# LTC3260.net
KiCad netlist of a schematic drawn in Altium Designer
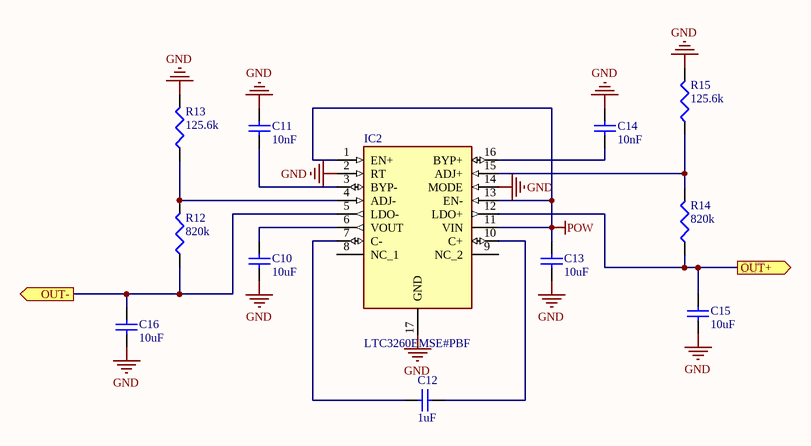
[diagram p0: LTC3260.SchDoc]

(export (version "E")
  (design (tool "Eeschema 10.0.6"))
  (components
    (comp (ref "C10")
      (value "10uF")
      (footprint "0805 CAP")
      (fields
        (field (name "MANUFACTURER") "Murata")
        (field (name "MANUFACTURER PART NUMBER") "GCM21BR7YA105KA55L")
      )
      (libsource (lib "charger_LT3652") (part "1uF/0805"))
    )
    (comp (ref "C11")
      (value "10nF")
      (footprint "0603 RES")
      (fields
        (field (name "MANUFACTURER") "Murata")
        (field (name "MANUFACTURER PART NUMBER") "GCM21BR7YA105KA55L")
      )
      (libsource (lib "charger_LT3652") (part "1uF/0805"))
    )
    (comp (ref "C12")
      (value "1uF")
      (footprint "0805 CAP")
      (fields
        (field (name "MANUFACTURER") "Murata")
        (field (name "MANUFACTURER PART NUMBER") "GCM21BR7YA105KA55L")
      )
      (libsource (lib "charger_LT3652") (part "1uF/0805"))
    )
    (comp (ref "C13")
      (value "10uF")
      (footprint "0805 CAP")
      (fields
        (field (name "MANUFACTURER") "Murata")
        (field (name "MANUFACTURER PART NUMBER") "GCM21BR7YA105KA55L")
      )
      (libsource (lib "charger_LT3652") (part "1uF/0805"))
    )
    (comp (ref "C14")
      (value "10nF")
      (footprint "0603 RES")
      (fields
        (field (name "MANUFACTURER") "Murata")
        (field (name "MANUFACTURER PART NUMBER") "GCM21BR7YA105KA55L")
      )
      (libsource (lib "charger_LT3652") (part "1uF/0805"))
    )
    (comp (ref "C15")
      (value "10uF")
      (footprint "0805 CAP")
      (fields
        (field (name "MANUFACTURER") "Murata")
        (field (name "MANUFACTURER PART NUMBER") "GCM21BR7YA105KA55L")
      )
      (libsource (lib "charger_LT3652") (part "1uF/0805"))
    )
    (comp (ref "C16")
      (value "10uF")
      (footprint "0805 CAP")
      (fields
        (field (name "MANUFACTURER") "Murata")
        (field (name "MANUFACTURER PART NUMBER") "GCM21BR7YA105KA55L")
      )
      (libsource (lib "charger_LT3652") (part "1uF/0805"))
    )
    (comp (ref "IC2")
      (value "LTC3260EMSE#PBF")
      (footprint "SOP50P490X110-17N")
      (description "Integrated Circuit")
      (fields
        (field (name "MOUSER PART NUMBER") "584-LTC3260EMSE#PBF")
        (field (name "RS PART NUMBER") "8516768P")
      )
      (libsource (lib "charger_LT3652") (part "LTC3260EMSE#PBF"))
    )
    (comp (ref "R12")
      (value "820k")
      (footprint "0603 RES")
      (description "Résistance standard")
      (fields (field (name "Comment") "Résistance") (field (name "DESIGNER") "ECAM 2005"))
      (libsource (lib "charger_LT3652") (part "Résistance"))
    )
    (comp (ref "R13")
      (value "125.6k")
      (footprint "0603 RES")
      (description "Résistance standard")
      (fields (field (name "Comment") "Résistance") (field (name "DESIGNER") "ECAM 2005"))
      (libsource (lib "charger_LT3652") (part "Résistance"))
    )
    (comp (ref "R14")
      (value "820k")
      (footprint "0603 RES")
      (description "Résistance standard")
      (fields (field (name "Comment") "Résistance") (field (name "DESIGNER") "ECAM 2005"))
      (libsource (lib "charger_LT3652") (part "Résistance"))
    )
    (comp (ref "R15")
      (value "125.6k")
      (footprint "0603 RES")
      (description "Résistance standard")
      (fields (field (name "Comment") "Résistance") (field (name "DESIGNER") "ECAM 2005"))
      (libsource (lib "charger_LT3652") (part "Résistance"))
    )
  )
  (nets
    (net (code "1") (name "/OUT+") (class "Default")
      (node (ref "C15") (pin "1") (pinfunction "1_1") (pintype "passive"))
      (node (ref "IC2") (pin "12") (pinfunction "LDO+_12") (pintype "output"))
      (node (ref "R14") (pin "1") (pinfunction "1_1") (pintype "passive"))
    )
    (net (code "2") (name "/OUT-") (class "Default")
      (node (ref "C16") (pin "1") (pinfunction "1_1") (pintype "passive"))
      (node (ref "IC2") (pin "5") (pinfunction "LDO-_5") (pintype "output"))
      (node (ref "R12") (pin "1") (pinfunction "1_1") (pintype "passive"))
    )
    (net (code "3") (name "GND") (class "Default")
      (node (ref "C10") (pin "2") (pinfunction "2_2") (pintype "passive"))
      (node (ref "C11") (pin "1") (pinfunction "1_1") (pintype "passive"))
      (node (ref "C13") (pin "1") (pinfunction "1_1") (pintype "passive"))
      (node (ref "C14") (pin "2") (pinfunction "2_2") (pintype "passive"))
      (node (ref "C15") (pin "2") (pinfunction "2_2") (pintype "passive"))
      (node (ref "C16") (pin "2") (pinfunction "2_2") (pintype "passive"))
      (node (ref "IC2") (pin "14") (pinfunction "MODE_14") (pintype "input"))
      (node (ref "IC2") (pin "17") (pinfunction "GND_17") (pintype "power_in"))
      (node (ref "IC2") (pin "2") (pinfunction "RT_2") (pintype "input"))
      (node (ref "R13") (pin "2") (pinfunction "2_2") (pintype "passive"))
      (node (ref "R15") (pin "2") (pinfunction "2_2") (pintype "passive"))
    )
    (net (code "4") (name "Net-(IC2-ADJ+)") (class "Default")
      (node (ref "IC2") (pin "15") (pinfunction "ADJ+_15") (pintype "input"))
      (node (ref "R14") (pin "2") (pinfunction "2_2") (pintype "passive"))
      (node (ref "R15") (pin "1") (pinfunction "1_1") (pintype "passive"))
    )
    (net (code "5") (name "Net-(IC2-ADJ-)") (class "Default")
      (node (ref "IC2") (pin "4") (pinfunction "ADJ-_4") (pintype "input"))
      (node (ref "R12") (pin "2") (pinfunction "2_2") (pintype "passive"))
      (node (ref "R13") (pin "1") (pinfunction "1_1") (pintype "passive"))
    )
    (net (code "6") (name "Net-(IC2-BYP+)") (class "Default")
      (node (ref "C14") (pin "1") (pinfunction "1_1") (pintype "passive"))
      (node (ref "IC2") (pin "16") (pinfunction "BYP+_16") (pintype "bidirectional"))
    )
    (net (code "7") (name "Net-(IC2-BYP-)") (class "Default")
      (node (ref "C11") (pin "2") (pinfunction "2_2") (pintype "passive"))
      (node (ref "IC2") (pin "3") (pinfunction "BYP-_3") (pintype "bidirectional"))
    )
    (net (code "8") (name "Net-(IC2-C+)") (class "Default")
      (node (ref "C12") (pin "2") (pinfunction "2_2") (pintype "passive"))
      (node (ref "IC2") (pin "10") (pinfunction "C+_10") (pintype "bidirectional"))
    )
    (net (code "9") (name "Net-(IC2-C-)") (class "Default")
      (node (ref "C12") (pin "1") (pinfunction "1_1") (pintype "passive"))
      (node (ref "IC2") (pin "7") (pinfunction "C-_7") (pintype "bidirectional"))
    )
    (net (code "10") (name "Net-(IC2-VOUT)") (class "Default")
      (node (ref "C10") (pin "1") (pinfunction "1_1") (pintype "passive"))
      (node (ref "IC2") (pin "6") (pinfunction "VOUT_6") (pintype "output"))
    )
    (net (code "11") (name "POW") (class "Default")
      (node (ref "C13") (pin "2") (pinfunction "2_2") (pintype "passive"))
      (node (ref "IC2") (pin "1") (pinfunction "EN+_1") (pintype "input"))
      (node (ref "IC2") (pin "11") (pinfunction "VIN_11") (pintype "power_in"))
      (node (ref "IC2") (pin "13") (pinfunction "EN-_13") (pintype "input"))
    )
    (net (code "12") (name "unconnected-(IC2-NC_1-Pad8)") (class "Default")
      (node (ref "IC2") (pin "8") (pinfunction "NC_1_8") (pintype "passive"))
    )
    (net (code "13") (name "unconnected-(IC2-NC_2-Pad9)") (class "Default")
      (node (ref "IC2") (pin "9") (pinfunction "NC_2_9") (pintype "passive"))
    )
  )
)
